# ATtiny_prog_board_with_USB.net
KiCad netlist of a schematic drawn in EAGLE
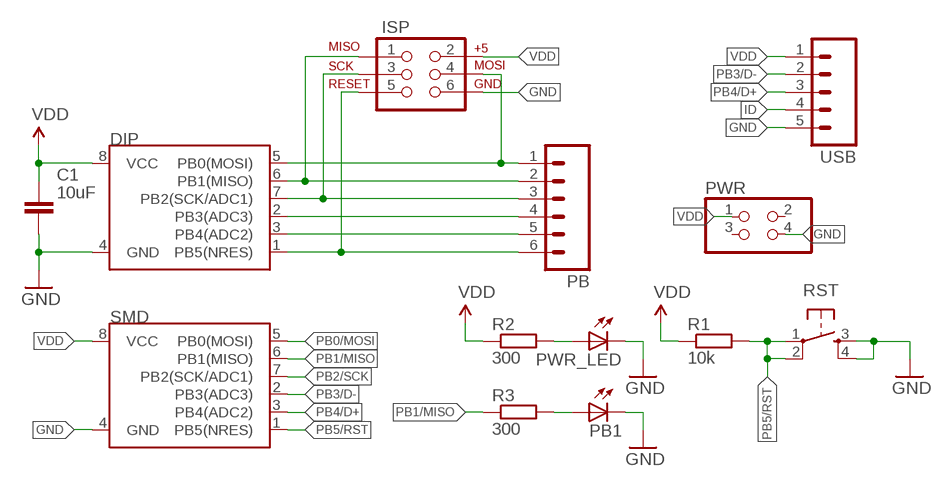
[diagram p0: schematic, sheet 1]

(export (version "E")
  (design (tool "Eeschema 10.0.6"))
  (components
    (comp (ref "C1")
      (value "10uF")
      (footprint "eagle-import:C805")
      (libsource (lib "eagle-import") (part "CAPACITOR_NPOL-0805"))
    )
    (comp (ref "DIP")
      (value "ATTINY45TINY85-20-DIP")
      (footprint "eagle-import:DIP08")
      (libsource (lib "eagle-import") (part "ATTINY45TINY85-20-DIP"))
    )
    (comp (ref "ISP")
      (value "AVR_SPI_PRG_6PTH")
      (footprint "eagle-import:2X3")
      (libsource (lib "eagle-import") (part "AVR_SPI_PRG_6PTH"))
    )
    (comp (ref "PB")
      (value "M06SILK_FEMALE_PTH")
      (footprint "eagle-import:1X06")
      (libsource (lib "eagle-import") (part "M06SILK_FEMALE_PTH"))
    )
    (comp (ref "PB1")
      (value "LED-0805")
      (footprint "eagle-import:LED-805")
      (libsource (lib "eagle-import") (part "LED-0805"))
    )
    (comp (ref "PWR")
      (value "PINHD-2X2")
      (footprint "eagle-import:2X02")
      (libsource (lib "eagle-import") (part "PINHD-2X2"))
    )
    (comp (ref "PWR_LED")
      (value "LED-0805")
      (footprint "eagle-import:LED-805")
      (libsource (lib "eagle-import") (part "LED-0805"))
    )
    (comp (ref "R1")
      (value "10k")
      (footprint "eagle-import:R603")
      (libsource (lib "eagle-import") (part "RESISTOR-0603"))
    )
    (comp (ref "R2")
      (value "300")
      (footprint "eagle-import:R603")
      (libsource (lib "eagle-import") (part "RESISTOR-0603"))
    )
    (comp (ref "R3")
      (value "300")
      (footprint "eagle-import:R603")
      (libsource (lib "eagle-import") (part "RESISTOR-0603"))
    )
    (comp (ref "RST")
      (value "TAC_SWITCHPTH")
      (footprint "eagle-import:TACTILE-PTH")
      (libsource (lib "eagle-import") (part "TAC_SWITCHPTH"))
    )
    (comp (ref "SMD")
      (value "ATTINY45TINY85-20-SMT")
      (footprint "eagle-import:SO08-EIAJ")
      (libsource (lib "eagle-import") (part "ATTINY45TINY85-20-SMT"))
    )
    (comp (ref "USB")
      (value "M05PTH")
      (footprint "eagle-import:1X05")
      (libsource (lib "eagle-import") (part "M05PTH"))
    )
  )
  (nets
    (net (code "1") (name "GND") (class "Default")
      (node (ref "C1") (pin "2") (pinfunction "2_2") (pintype "passive"))
      (node (ref "DIP") (pin "4") (pinfunction "GND_4") (pintype "bidirectional"))
      (node (ref "ISP") (pin "6") (pinfunction "6_6") (pintype "passive"))
      (node (ref "PB1") (pin "C") (pinfunction "C_C") (pintype "passive"))
      (node (ref "PWR") (pin "4") (pinfunction "4_4") (pintype "passive"))
      (node (ref "PWR_LED") (pin "C") (pinfunction "C_C") (pintype "passive"))
      (node (ref "RST") (pin "3") (pinfunction "3_3") (pintype "passive"))
      (node (ref "RST") (pin "4") (pinfunction "4_4") (pintype "passive"))
      (node (ref "SMD") (pin "4") (pinfunction "GND_4") (pintype "bidirectional"))
      (node (ref "USB") (pin "5") (pinfunction "5_5") (pintype "passive"))
    )
    (net (code "2") (name "ID") (class "Default")
      (node (ref "USB") (pin "4") (pinfunction "4_4") (pintype "passive"))
    )
    (net (code "3") (name "Net-(PB1-PadA)") (class "Default")
      (node (ref "PB1") (pin "A") (pinfunction "A_A") (pintype "passive"))
      (node (ref "R3") (pin "2") (pinfunction "2_2") (pintype "passive"))
    )
    (net (code "4") (name "Net-(PWR_LED-PadA)") (class "Default")
      (node (ref "PWR_LED") (pin "A") (pinfunction "A_A") (pintype "passive"))
      (node (ref "R2") (pin "2") (pinfunction "2_2") (pintype "passive"))
    )
    (net (code "5") (name "PB0{slash}MOSI") (class "Default")
      (node (ref "DIP") (pin "5") (pinfunction "PB0(MOSI)_5") (pintype "bidirectional"))
      (node (ref "ISP") (pin "4") (pinfunction "4_4") (pintype "passive"))
      (node (ref "PB") (pin "1") (pinfunction "1_1") (pintype "passive"))
      (node (ref "SMD") (pin "5") (pinfunction "PB0(MOSI)_5") (pintype "bidirectional"))
    )
    (net (code "6") (name "PB1{slash}MISO") (class "Default")
      (node (ref "DIP") (pin "6") (pinfunction "PB1(MISO)_6") (pintype "bidirectional"))
      (node (ref "ISP") (pin "1") (pinfunction "1_1") (pintype "passive"))
      (node (ref "PB") (pin "2") (pinfunction "2_2") (pintype "passive"))
      (node (ref "R3") (pin "1") (pinfunction "1_1") (pintype "passive"))
      (node (ref "SMD") (pin "6") (pinfunction "PB1(MISO)_6") (pintype "bidirectional"))
    )
    (net (code "7") (name "PB2{slash}SCK") (class "Default")
      (node (ref "DIP") (pin "7") (pinfunction "PB2(SCK/ADC1)_7") (pintype "bidirectional"))
      (node (ref "ISP") (pin "3") (pinfunction "3_3") (pintype "passive"))
      (node (ref "PB") (pin "3") (pinfunction "3_3") (pintype "passive"))
      (node (ref "SMD") (pin "7") (pinfunction "PB2(SCK/ADC1)_7") (pintype "bidirectional"))
    )
    (net (code "8") (name "PB3{slash}D-") (class "Default")
      (node (ref "DIP") (pin "2") (pinfunction "PB3(ADC3)_2") (pintype "bidirectional"))
      (node (ref "PB") (pin "4") (pinfunction "4_4") (pintype "passive"))
      (node (ref "SMD") (pin "2") (pinfunction "PB3(ADC3)_2") (pintype "bidirectional"))
      (node (ref "USB") (pin "2") (pinfunction "2_2") (pintype "passive"))
    )
    (net (code "9") (name "PB4{slash}D+") (class "Default")
      (node (ref "DIP") (pin "3") (pinfunction "PB4(ADC2)_3") (pintype "bidirectional"))
      (node (ref "PB") (pin "5") (pinfunction "5_5") (pintype "passive"))
      (node (ref "SMD") (pin "3") (pinfunction "PB4(ADC2)_3") (pintype "bidirectional"))
      (node (ref "USB") (pin "3") (pinfunction "3_3") (pintype "passive"))
    )
    (net (code "10") (name "PB5{slash}RST") (class "Default")
      (node (ref "DIP") (pin "1") (pinfunction "PB5(NRES)_1") (pintype "bidirectional"))
      (node (ref "ISP") (pin "5") (pinfunction "5_5") (pintype "passive"))
      (node (ref "PB") (pin "6") (pinfunction "6_6") (pintype "passive"))
      (node (ref "R1") (pin "2") (pinfunction "2_2") (pintype "passive"))
      (node (ref "RST") (pin "1") (pinfunction "1_1") (pintype "passive"))
      (node (ref "RST") (pin "2") (pinfunction "2_2") (pintype "passive"))
      (node (ref "SMD") (pin "1") (pinfunction "PB5(NRES)_1") (pintype "bidirectional"))
    )
    (net (code "11") (name "VDD") (class "Default")
      (node (ref "C1") (pin "1") (pinfunction "1_1") (pintype "passive"))
      (node (ref "DIP") (pin "8") (pinfunction "VCC_8") (pintype "bidirectional"))
      (node (ref "ISP") (pin "2") (pinfunction "2_2") (pintype "passive"))
      (node (ref "PWR") (pin "1") (pinfunction "1_1") (pintype "passive"))
      (node (ref "R1") (pin "1") (pinfunction "1_1") (pintype "passive"))
      (node (ref "R2") (pin "1") (pinfunction "1_1") (pintype "passive"))
      (node (ref "SMD") (pin "8") (pinfunction "VCC_8") (pintype "bidirectional"))
      (node (ref "USB") (pin "1") (pinfunction "1_1") (pintype "passive"))
    )
    (net (code "12") (name "unconnected-(PWR-Pad2)") (class "Default")
      (node (ref "PWR") (pin "2") (pinfunction "2_2") (pintype "passive"))
    )
    (net (code "13") (name "unconnected-(PWR-Pad3)") (class "Default")
      (node (ref "PWR") (pin "3") (pinfunction "3_3") (pintype "passive"))
    )
  )
)
